# OctopusBotV3R1.net
KiCad netlist of a schematic drawn in Altium Designer
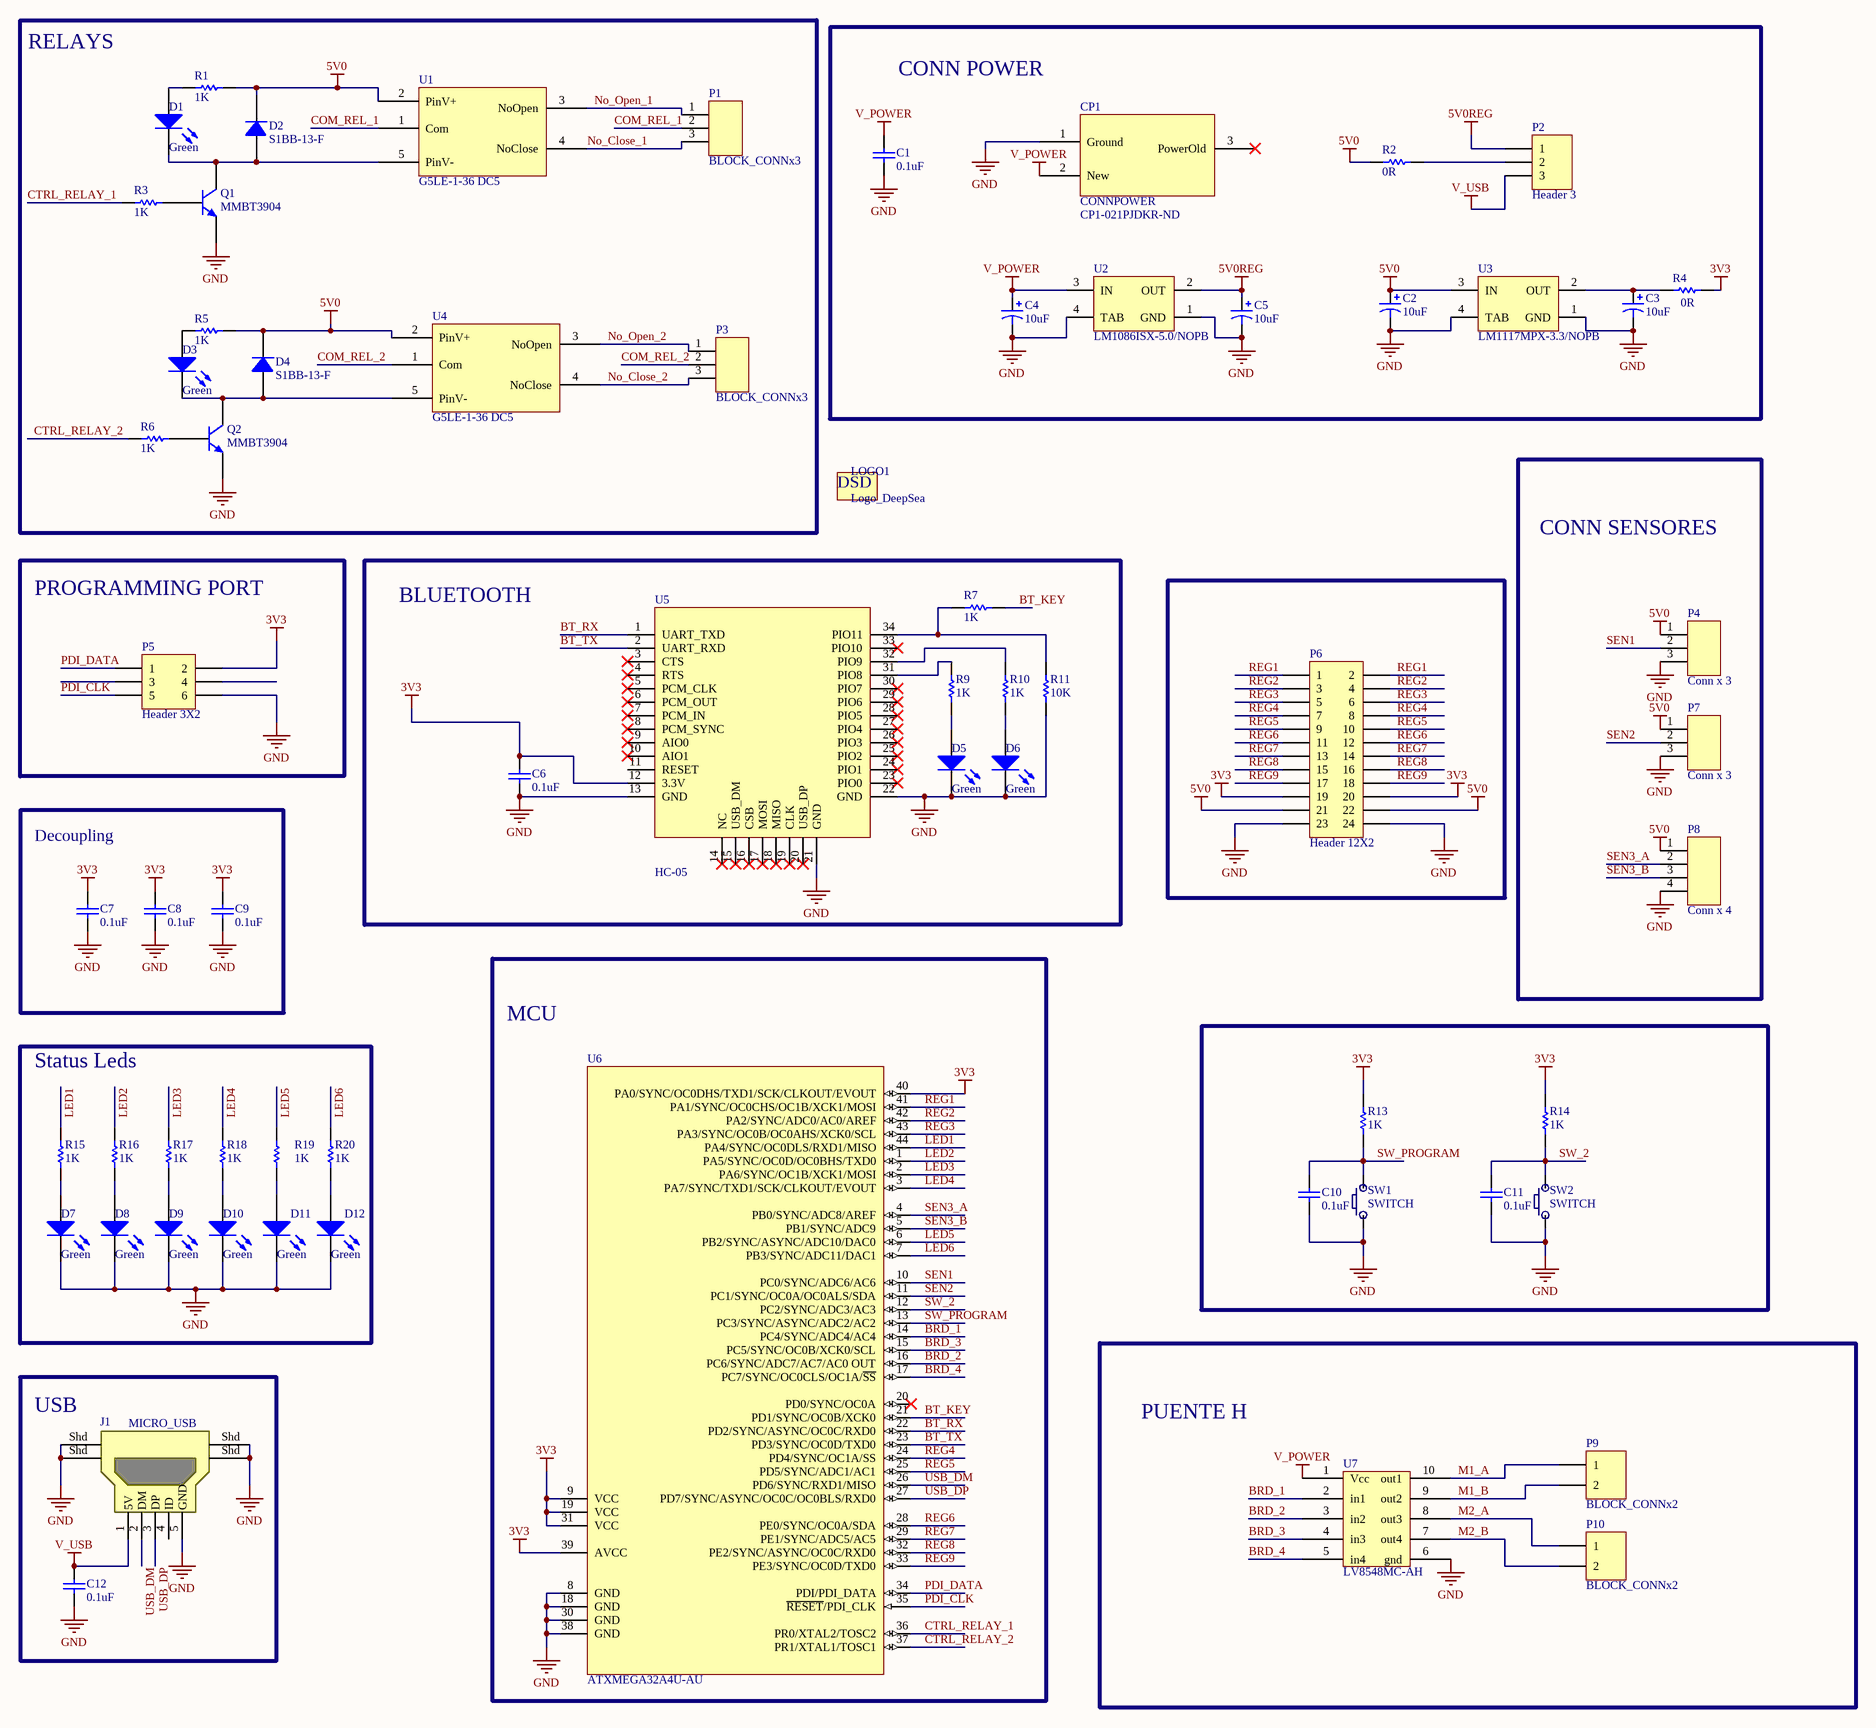
[diagram p0: OctopusBotV3R1.SchDoc]

(export (version "E")
  (design (tool "Eeschema 10.0.6"))
  (components
    (comp (ref "C1") (value "0.1uF") (footprint "C0603_N") (libsource (lib "General") (part "C_SMD")))
    (comp (ref "C2") (value "10uF") (footprint "C_TANT_A_3216_N") (libsource (lib "General") (part "CP_SMD")))
    (comp (ref "C3") (value "10uF") (footprint "C_TANT_A_3216_N") (libsource (lib "General") (part "CP_SMD")))
    (comp (ref "C4") (value "10uF") (footprint "C_TANT_A_3216_N") (libsource (lib "General") (part "CP_SMD")))
    (comp (ref "C5") (value "10uF") (footprint "C_TANT_A_3216_N") (libsource (lib "General") (part "CP_SMD")))
    (comp (ref "C6") (value "0.1uF") (footprint "C0603_N") (libsource (lib "General") (part "C_SMD")))
    (comp (ref "C7") (value "0.1uF") (footprint "C0603_N") (libsource (lib "General") (part "C_SMD")))
    (comp (ref "C8") (value "0.1uF") (footprint "C0603_N") (libsource (lib "General") (part "C_SMD")))
    (comp (ref "C9") (value "0.1uF") (footprint "C0603_N") (libsource (lib "General") (part "C_SMD")))
    (comp (ref "C10") (value "0.1uF") (footprint "C0603_N") (libsource (lib "General") (part "C_SMD")))
    (comp (ref "C11") (value "0.1uF") (footprint "C0603_N") (libsource (lib "General") (part "C_SMD")))
    (comp (ref "C12") (value "0.1uF") (footprint "C0603_N") (libsource (lib "General") (part "C_SMD")))
    (comp (ref "CP1")
      (value "CONNPOWER")
      (footprint "CONNPOWER")
      (fields (field (name "SUPPLIER PART NUMBER 1") "CP1-021PJDKR-ND"))
      (libsource (lib "General") (part "CONNPOWER"))
    )
    (comp (ref "D1")
      (value "Green")
      (footprint "R0603_N")
      (fields (field (name "COLOR") "Green"))
      (libsource (lib "discrete") (part "LED_SMD"))
    )
    (comp (ref "D2")
      (value "S1BB-13-F")
      (footprint "SMB_M")
      (description "DIODE GEN PURPOSE 100V 1A SMB")
      (fields (field (name "MANUFACTURER") "Diodes Incorporated"))
      (libsource (lib "General") (part "S1BB-13-F"))
    )
    (comp (ref "D3")
      (value "Green")
      (footprint "R0603_N")
      (fields (field (name "COLOR") "Green"))
      (libsource (lib "discrete") (part "LED_SMD"))
    )
    (comp (ref "D4")
      (value "S1BB-13-F")
      (footprint "SMB_M")
      (description "DIODE GEN PURPOSE 100V 1A SMB")
      (fields (field (name "MANUFACTURER") "Diodes Incorporated"))
      (libsource (lib "General") (part "S1BB-13-F"))
    )
    (comp (ref "D5")
      (value "Green")
      (footprint "R0603_N")
      (fields (field (name "COLOR") "Green"))
      (libsource (lib "discrete") (part "LED_SMD"))
    )
    (comp (ref "D6")
      (value "Green")
      (footprint "R0603_N")
      (fields (field (name "COLOR") "Green"))
      (libsource (lib "discrete") (part "LED_SMD"))
    )
    (comp (ref "D7")
      (value "Green")
      (footprint "R0603_N")
      (fields (field (name "COLOR") "Green"))
      (libsource (lib "discrete") (part "LED_SMD"))
    )
    (comp (ref "D8")
      (value "Green")
      (footprint "R0603_N")
      (fields (field (name "COLOR") "Green"))
      (libsource (lib "discrete") (part "LED_SMD"))
    )
    (comp (ref "D9")
      (value "Green")
      (footprint "R0603_N")
      (fields (field (name "COLOR") "Green"))
      (libsource (lib "discrete") (part "LED_SMD"))
    )
    (comp (ref "D10")
      (value "Green")
      (footprint "R0603_N")
      (fields (field (name "COLOR") "Green"))
      (libsource (lib "discrete") (part "LED_SMD"))
    )
    (comp (ref "D11")
      (value "Green")
      (footprint "R0603_N")
      (fields (field (name "COLOR") "Green"))
      (libsource (lib "discrete") (part "LED_SMD"))
    )
    (comp (ref "D12")
      (value "Green")
      (footprint "R0603_N")
      (fields (field (name "COLOR") "Green"))
      (libsource (lib "discrete") (part "LED_SMD"))
    )
    (comp (ref "J1")
      (value "MICRO_USB")
      (footprint "USB_MICRO_SMD")
      (description "CONN USB MICRO B RECPT SMT R/A")
      (fields (field (name "MANUFACTURER") "FCI") (field (name "MANUFACTURER PART NUMBER") "10118194-0001LF"))
      (libsource (lib "General") (part "MICRO_USB"))
    )
    (comp (ref "LOGO1")
      (value "Logo_DeepSea")
      (footprint "DeepSea_logo1")
      (libsource (lib "General") (part "Logo_DeepSea"))
    )
    (comp (ref "P1")
      (value "BLOCK_CONNx3")
      (footprint "BLOCK_CONNx3")
      (description "TERM BLOCK 5.08MM VERT 3POS PCB")
      (fields
        (field (name "MANUFACTURER") "On Shore Technology Inc")
        (field (name "MANUFACTURER PART NUMBER") "OSTTC032162")
      )
      (libsource (lib "General") (part "BLOCK_CONNx3"))
    )
    (comp (ref "P2")
      (value "Header 3")
      (footprint "HDR1X3")
      (description "Header, 3-Pin")
      (fields (field (name "PUBLISHER") "Altium Limited"))
      (libsource (lib "Miscellaneous Connectors") (part "Header 3"))
    )
    (comp (ref "P3")
      (value "BLOCK_CONNx3")
      (footprint "BLOCK_CONNx3")
      (description "TERM BLOCK 5.08MM VERT 3POS PCB")
      (fields
        (field (name "MANUFACTURER") "On Shore Technology Inc")
        (field (name "MANUFACTURER PART NUMBER") "OSTTC032162")
      )
      (libsource (lib "General") (part "BLOCK_CONNx3"))
    )
    (comp (ref "P4")
      (value "Conn x 3")
      (footprint "conn x 3")
      (description "CONN HEADER VERT 3POS .100 TIN")
      (fields
        (field (name "MANUFACTURER") "TE Connectivity")
        (field (name "MANUFACTURER PART NUMBER") "640456-3")
      )
      (libsource (lib "General") (part "Conn x 3"))
    )
    (comp (ref "P5")
      (value "Header 3X2")
      (footprint "HDR2X3")
      (description "Header, 3-Pin, Dual row")
      (fields (field (name "PUBLISHER") "Altium Limited"))
      (libsource (lib "Miscellaneous Connectors") (part "Header 3X2"))
    )
    (comp (ref "P6")
      (value "Header 12X2")
      (footprint "HDR2X12")
      (description "Header, 12-Pin, Dual row")
      (fields (field (name "PUBLISHER") "Altium Limited"))
      (libsource (lib "Miscellaneous Connectors") (part "Header 12X2"))
    )
    (comp (ref "P7")
      (value "Conn x 3")
      (footprint "conn x 3")
      (description "CONN HEADER VERT 3POS .100 TIN")
      (fields
        (field (name "MANUFACTURER") "TE Connectivity")
        (field (name "MANUFACTURER PART NUMBER") "640456-3")
      )
      (libsource (lib "General") (part "Conn x 3"))
    )
    (comp (ref "P8")
      (value "Conn x 4")
      (footprint "conn x 4")
      (description "CONN HEADER VERT 4POS .100 TIN")
      (fields
        (field (name "MANUFACTURER") "TE Connectivity")
        (field (name "MANUFACTURER PART NUMBER") "640454-4")
      )
      (libsource (lib "General") (part "Conn x 4"))
    )
    (comp (ref "P9")
      (value "BLOCK_CONNx2")
      (footprint "BLOCK_CONNX2")
      (description "TERM BLOCK 5.08MM VERT 2POS PCB")
      (fields
        (field (name "MANUFACTURER") "On Shore Technology Inc")
        (field (name "MANUFACTURER PART NUMBER") "OSTTC022162")
      )
      (libsource (lib "General") (part "BLOCK_CONNx2"))
    )
    (comp (ref "P10")
      (value "BLOCK_CONNx2")
      (footprint "BLOCK_CONNX2")
      (description "TERM BLOCK 5.08MM VERT 2POS PCB")
      (fields
        (field (name "MANUFACTURER") "On Shore Technology Inc")
        (field (name "MANUFACTURER PART NUMBER") "OSTTC022162")
      )
      (libsource (lib "General") (part "BLOCK_CONNx2"))
    )
    (comp (ref "Q1")
      (value "MMBT3904")
      (footprint "SOT23_N")
      (description "NPN Switching Transistor")
      (fields
        (field (name "MANUFACTURER") "Micro Commercial Co")
        (field (name "MANUFACTURER PART NUMBER") "MMBT3904-TP")
        (field (name "PUBLISHER") "Altium Limited")
      )
      (libsource (lib "General") (part "MMBT3904"))
    )
    (comp (ref "Q2")
      (value "MMBT3904")
      (footprint "SOT23_N")
      (description "NPN Switching Transistor")
      (fields
        (field (name "MANUFACTURER") "Micro Commercial Co")
        (field (name "MANUFACTURER PART NUMBER") "MMBT3904-TP")
        (field (name "PUBLISHER") "Altium Limited")
      )
      (libsource (lib "General") (part "MMBT3904"))
    )
    (comp (ref "R1") (value "1K") (footprint "R0603_N") (libsource (lib "discrete") (part "R_SMD")))
    (comp (ref "R2") (value "0R") (footprint "R0603_N") (libsource (lib "discrete") (part "R_SMD")))
    (comp (ref "R3") (value "1K") (footprint "R0603_N") (libsource (lib "discrete") (part "R_SMD")))
    (comp (ref "R4") (value "0R") (footprint "R0603_N") (libsource (lib "discrete") (part "R_SMD")))
    (comp (ref "R5") (value "1K") (footprint "R0603_N") (libsource (lib "discrete") (part "R_SMD")))
    (comp (ref "R6") (value "1K") (footprint "R0603_N") (libsource (lib "discrete") (part "R_SMD")))
    (comp (ref "R7") (value "1K") (footprint "R0603_N") (libsource (lib "discrete") (part "R_SMD")))
    (comp (ref "R9") (value "1K") (footprint "R0603_N") (libsource (lib "discrete") (part "R_SMD")))
    (comp (ref "R10") (value "1K") (footprint "R0603_N") (libsource (lib "discrete") (part "R_SMD")))
    (comp (ref "R11") (value "10K") (footprint "R0603_N") (libsource (lib "discrete") (part "R_SMD")))
    (comp (ref "R13") (value "1K") (footprint "R0603_N") (libsource (lib "discrete") (part "R_SMD")))
    (comp (ref "R14") (value "1K") (footprint "R0603_N") (libsource (lib "discrete") (part "R_SMD")))
    (comp (ref "R15") (value "1K") (footprint "R0603_N") (libsource (lib "discrete") (part "R_SMD")))
    (comp (ref "R16") (value "1K") (footprint "R0603_N") (libsource (lib "discrete") (part "R_SMD")))
    (comp (ref "R17") (value "1K") (footprint "R0603_N") (libsource (lib "discrete") (part "R_SMD")))
    (comp (ref "R18") (value "1K") (footprint "R0603_N") (libsource (lib "discrete") (part "R_SMD")))
    (comp (ref "R19") (value "1K") (footprint "R0603_N") (libsource (lib "discrete") (part "R_SMD")))
    (comp (ref "R20") (value "1K") (footprint "R0603_N") (libsource (lib "discrete") (part "R_SMD")))
    (comp (ref "SW1")
      (value "SWITCH")
      (footprint "swich_foot")
      (description "SWITCH TACTILE SPST-NO 0.05A 12V")
      (fields
        (field (name "MANUFACTURER") "TE Connectivity")
        (field (name "MANUFACTURER PART NUMBER") "FSM4JSMATR")
      )
      (libsource (lib "General") (part "SWITCH"))
    )
    (comp (ref "SW2")
      (value "SWITCH")
      (footprint "swich_foot")
      (description "SWITCH TACTILE SPST-NO 0.05A 12V")
      (fields
        (field (name "MANUFACTURER") "TE Connectivity")
        (field (name "MANUFACTURER PART NUMBER") "FSM4JSMATR")
      )
      (libsource (lib "General") (part "SWITCH"))
    )
    (comp (ref "U1")
      (value "G5LE-1-36 DC5")
      (footprint "Relay 5V")
      (description "RELAY GEN PURPOSE SPDT 10A 5V")
      (fields (field (name "MANUFACTURER") "Omron Electronics Inc-EMC Div"))
      (libsource (lib "General") (part "G5LE-1-36 DC5"))
    )
    (comp (ref "U2")
      (value "LM1086ISX-5.0/NOPB")
      (footprint "TS3B_N")
      (description "1.5A Low Dropout Positive Regulators, 3-pin TO-263, Pb-Free")
      (fields
        (field (name "MANUFACTURER") "National Semiconductor")
        (field (name "PUBLISHER") "Altium Limited")
      )
      (libsource (lib "General") (part "LM1086ISX-5.0/NOPB"))
    )
    (comp (ref "U3")
      (value "LM1117MPX-3.3/NOPB")
      (footprint "MP04A_N")
      (description "800mA Low-Dropout Linear Regulator, 4-pin SOT-223, Pb-Free")
      (fields
        (field (name "MANUFACTURER") "National Semiconductor")
        (field (name "PUBLISHER") "Altium Limited")
      )
      (libsource (lib "General") (part "LM1117MPX-3.3/NOPB"))
    )
    (comp (ref "U4")
      (value "G5LE-1-36 DC5")
      (footprint "Relay 5V")
      (description "RELAY GEN PURPOSE SPDT 10A 5V")
      (fields (field (name "MANUFACTURER") "Omron Electronics Inc-EMC Div"))
      (libsource (lib "General") (part "G5LE-1-36 DC5"))
    )
    (comp (ref "U5")
      (value "HC-05")
      (footprint "HC-05")
      (description "Bluetooth RS232 module")
      (libsource (lib "General") (part "HC-05"))
    )
    (comp (ref "U6")
      (value "ATXMEGA32A4U-AU")
      (footprint "44A_N")
      (description "IC MCU 8BIT 32KB FLASH 44TQFP")
      (fields (field (name "MANUFACTURER") "Atmel"))
      (libsource (lib "General") (part "ATXMEGA32A4U-AU"))
    )
    (comp (ref "U7")
      (value "LV8548MC-AH")
      (footprint "SOIC10")
      (description "IC MOTOR DRIVER PAR MFP10S")
      (fields (field (name "MANUFACTURER") "ON Semiconductor"))
      (libsource (lib "General") (part "LV8548MC-AH"))
    )
  )
  (nets
    (net (code "1") (name "/BRD_1") (class "Default")
      (node (ref "U6") (pin "14") (pinfunction "PC4/SYNC/ADC4/AC4_14") (pintype "bidirectional"))
      (node (ref "U7") (pin "2") (pinfunction "in1_2") (pintype "passive"))
    )
    (net (code "2") (name "/BRD_2") (class "Default")
      (node (ref "U6") (pin "16") (pinfunction "PC6/SYNC/ADC7/AC7/AC0_OUT_16") (pintype "bidirectional"))
      (node (ref "U7") (pin "3") (pinfunction "in2_3") (pintype "passive"))
    )
    (net (code "3") (name "/BRD_3") (class "Default")
      (node (ref "U6") (pin "15") (pinfunction "PC5/SYNC/OC0B/XCK0/SCL_15") (pintype "bidirectional"))
      (node (ref "U7") (pin "4") (pinfunction "in3_4") (pintype "passive"))
    )
    (net (code "4") (name "/BRD_4") (class "Default")
      (node (ref "U6") (pin "17") (pinfunction "PC7/SYNC/OC0CLS/OC1A/~{SS}_17") (pintype "bidirectional"))
      (node (ref "U7") (pin "5") (pinfunction "in4_5") (pintype "passive"))
    )
    (net (code "5") (name "/BT_KEY") (class "Default")
      (node (ref "R7") (pin "1") (pinfunction "1_1") (pintype "passive"))
      (node (ref "U6") (pin "21") (pinfunction "PD1/SYNC/OC0B/XCK0_21") (pintype "bidirectional"))
    )
    (net (code "6") (name "/BT_RX") (class "Default")
      (node (ref "U5") (pin "1") (pinfunction "UART_TXD_1") (pintype "passive"))
      (node (ref "U6") (pin "22") (pinfunction "PD2/SYNC/ASYNC/OC0C/RXD0_22") (pintype "bidirectional"))
    )
    (net (code "7") (name "/BT_TX") (class "Default")
      (node (ref "U5") (pin "2") (pinfunction "UART_RXD_2") (pintype "passive"))
      (node (ref "U6") (pin "23") (pinfunction "PD3/SYNC/OC0D/TXD0_23") (pintype "bidirectional"))
    )
    (net (code "8") (name "/COM_REL_1") (class "Default")
      (node (ref "P1") (pin "2") (pintype "passive"))
      (node (ref "U1") (pin "1") (pinfunction "Com_1") (pintype "passive"))
    )
    (net (code "9") (name "/COM_REL_2") (class "Default")
      (node (ref "P3") (pin "2") (pintype "passive"))
      (node (ref "U4") (pin "1") (pinfunction "Com_1") (pintype "passive"))
    )
    (net (code "10") (name "/CTRL_RELAY_1") (class "Default")
      (node (ref "R3") (pin "1") (pinfunction "1_1") (pintype "passive"))
      (node (ref "U6") (pin "36") (pinfunction "PR0/XTAL2/TOSC2_36") (pintype "bidirectional"))
    )
    (net (code "11") (name "/CTRL_RELAY_2") (class "Default")
      (node (ref "R6") (pin "1") (pinfunction "1_1") (pintype "passive"))
      (node (ref "U6") (pin "37") (pinfunction "PR1/XTAL1/TOSC1_37") (pintype "bidirectional"))
    )
    (net (code "12") (name "/LED1") (class "Default")
      (node (ref "R15") (pin "1") (pinfunction "1_1") (pintype "passive"))
      (node (ref "U6") (pin "44") (pinfunction "PA4/SYNC/OC0DLS/RXD1/MISO_44") (pintype "bidirectional"))
    )
    (net (code "13") (name "/LED2") (class "Default")
      (node (ref "R16") (pin "1") (pinfunction "1_1") (pintype "passive"))
      (node (ref "U6") (pin "1") (pinfunction "PA5/SYNC/OC0D/OC0BHS/TXD0_1") (pintype "bidirectional"))
    )
    (net (code "14") (name "/LED3") (class "Default")
      (node (ref "R17") (pin "1") (pinfunction "1_1") (pintype "passive"))
      (node (ref "U6") (pin "2") (pinfunction "PA6/SYNC/OC1B/XCK1/MOSI_2") (pintype "bidirectional"))
    )
    (net (code "15") (name "/LED4") (class "Default")
      (node (ref "R18") (pin "1") (pinfunction "1_1") (pintype "passive"))
      (node (ref "U6") (pin "3") (pinfunction "PA7/SYNC/TXD1/SCK/CLKOUT/EVOUT_3") (pintype "bidirectional"))
    )
    (net (code "16") (name "/LED5") (class "Default")
      (node (ref "R19") (pin "1") (pinfunction "1_1") (pintype "passive"))
      (node (ref "U6") (pin "6") (pinfunction "PB2/SYNC/ASYNC/ADC10/DAC0_6") (pintype "bidirectional"))
    )
    (net (code "17") (name "/LED6") (class "Default")
      (node (ref "R20") (pin "1") (pinfunction "1_1") (pintype "passive"))
      (node (ref "U6") (pin "7") (pinfunction "PB3/SYNC/ADC11/DAC1_7") (pintype "bidirectional"))
    )
    (net (code "18") (name "/M1_A") (class "Default")
      (node (ref "P9") (pin "1") (pinfunction "1_1") (pintype "passive"))
      (node (ref "U7") (pin "10") (pinfunction "out1_10") (pintype "passive"))
    )
    (net (code "19") (name "/M1_B") (class "Default")
      (node (ref "P9") (pin "2") (pinfunction "2_2") (pintype "passive"))
      (node (ref "U7") (pin "9") (pinfunction "out2_9") (pintype "passive"))
    )
    (net (code "20") (name "/M2_A") (class "Default")
      (node (ref "P10") (pin "1") (pinfunction "1_1") (pintype "passive"))
      (node (ref "U7") (pin "8") (pinfunction "out3_8") (pintype "passive"))
    )
    (net (code "21") (name "/M2_B") (class "Default")
      (node (ref "P10") (pin "2") (pinfunction "2_2") (pintype "passive"))
      (node (ref "U7") (pin "7") (pinfunction "out4_7") (pintype "passive"))
    )
    (net (code "22") (name "/No_Close_1") (class "Default")
      (node (ref "P1") (pin "3") (pintype "passive"))
      (node (ref "U1") (pin "4") (pinfunction "NoClose_4") (pintype "passive"))
    )
    (net (code "23") (name "/No_Close_2") (class "Default")
      (node (ref "P3") (pin "3") (pintype "passive"))
      (node (ref "U4") (pin "4") (pinfunction "NoClose_4") (pintype "passive"))
    )
    (net (code "24") (name "/No_Open_1") (class "Default")
      (node (ref "P1") (pin "1") (pintype "passive"))
      (node (ref "U1") (pin "3") (pinfunction "NoOpen_3") (pintype "passive"))
    )
    (net (code "25") (name "/No_Open_2") (class "Default")
      (node (ref "P3") (pin "1") (pintype "passive"))
      (node (ref "U4") (pin "3") (pinfunction "NoOpen_3") (pintype "passive"))
    )
    (net (code "26") (name "/PDI_CLK") (class "Default")
      (node (ref "P5") (pin "5") (pinfunction "5_5") (pintype "passive"))
      (node (ref "U6") (pin "35") (pinfunction "~{RESET}/PDI_CLK_35") (pintype "input"))
    )
    (net (code "27") (name "/PDI_DATA") (class "Default")
      (node (ref "P5") (pin "1") (pinfunction "1_1") (pintype "passive"))
      (node (ref "U6") (pin "34") (pinfunction "PDI/PDI_DATA_34") (pintype "bidirectional"))
    )
    (net (code "28") (name "/REG1") (class "Default")
      (node (ref "P6") (pin "1") (pinfunction "1_1") (pintype "passive"))
      (node (ref "P6") (pin "2") (pinfunction "2_2") (pintype "passive"))
      (node (ref "U6") (pin "41") (pinfunction "PA1/SYNC/OC0CHS/OC1B/XCK1/MOSI_41") (pintype "bidirectional"))
    )
    (net (code "29") (name "/REG2") (class "Default")
      (node (ref "P6") (pin "3") (pinfunction "3_3") (pintype "passive"))
      (node (ref "P6") (pin "4") (pinfunction "4_4") (pintype "passive"))
      (node (ref "U6") (pin "42") (pinfunction "PA2/SYNC/ADC0/AC0/AREF_42") (pintype "bidirectional"))
    )
    (net (code "30") (name "/REG3") (class "Default")
      (node (ref "P6") (pin "5") (pinfunction "5_5") (pintype "passive"))
      (node (ref "P6") (pin "6") (pinfunction "6_6") (pintype "passive"))
      (node (ref "U6") (pin "43") (pinfunction "PA3/SYNC/OC0B/OC0AHS/XCK0/SCL_43") (pintype "bidirectional"))
    )
    (net (code "31") (name "/REG4") (class "Default")
      (node (ref "P6") (pin "7") (pinfunction "7_7") (pintype "passive"))
      (node (ref "P6") (pin "8") (pinfunction "8_8") (pintype "passive"))
      (node (ref "U6") (pin "24") (pinfunction "PD4/SYNC/OC1A/SS_24") (pintype "bidirectional"))
    )
    (net (code "32") (name "/REG5") (class "Default")
      (node (ref "P6") (pin "10") (pinfunction "10_10") (pintype "passive"))
      (node (ref "P6") (pin "9") (pinfunction "9_9") (pintype "passive"))
      (node (ref "U6") (pin "25") (pinfunction "PD5/SYNC/ADC1/AC1_25") (pintype "bidirectional"))
    )
    (net (code "33") (name "/REG6") (class "Default")
      (node (ref "P6") (pin "11") (pinfunction "11_11") (pintype "passive"))
      (node (ref "P6") (pin "12") (pinfunction "12_12") (pintype "passive"))
      (node (ref "U6") (pin "28") (pinfunction "PE0/SYNC/OC0A/SDA_28") (pintype "bidirectional"))
    )
    (net (code "34") (name "/REG7") (class "Default")
      (node (ref "P6") (pin "13") (pinfunction "13_13") (pintype "passive"))
      (node (ref "P6") (pin "14") (pinfunction "14_14") (pintype "passive"))
      (node (ref "U6") (pin "29") (pinfunction "PE1/SYNC/ADC5/AC5_29") (pintype "bidirectional"))
    )
    (net (code "35") (name "/REG8") (class "Default")
      (node (ref "P6") (pin "15") (pinfunction "15_15") (pintype "passive"))
      (node (ref "P6") (pin "16") (pinfunction "16_16") (pintype "passive"))
      (node (ref "U6") (pin "32") (pinfunction "PE2/SYNC/ASYNC/OC0C/RXD0_32") (pintype "bidirectional"))
    )
    (net (code "36") (name "/REG9") (class "Default")
      (node (ref "P6") (pin "17") (pinfunction "17_17") (pintype "passive"))
      (node (ref "P6") (pin "18") (pinfunction "18_18") (pintype "passive"))
      (node (ref "U6") (pin "33") (pinfunction "PE3/SYNC/OC0D/TXD0_33") (pintype "bidirectional"))
    )
    (net (code "37") (name "/SEN1") (class "Default")
      (node (ref "P4") (pin "2") (pintype "passive"))
      (node (ref "U6") (pin "10") (pinfunction "PC0/SYNC/ADC6/AC6_10") (pintype "bidirectional"))
    )
    (net (code "38") (name "/SEN2") (class "Default")
      (node (ref "P7") (pin "2") (pintype "passive"))
      (node (ref "U6") (pin "11") (pinfunction "PC1/SYNC/OC0A/OC0ALS/SDA_11") (pintype "bidirectional"))
    )
    (net (code "39") (name "/SEN3_A") (class "Default")
      (node (ref "P8") (pin "2") (pintype "passive"))
      (node (ref "U6") (pin "4") (pinfunction "PB0/SYNC/ADC8/AREF_4") (pintype "bidirectional"))
    )
    (net (code "40") (name "/SEN3_B") (class "Default")
      (node (ref "P8") (pin "3") (pintype "passive"))
      (node (ref "U6") (pin "5") (pinfunction "PB1/SYNC/ADC9_5") (pintype "bidirectional"))
    )
    (net (code "41") (name "/SW_2") (class "Default")
      (node (ref "C11") (pin "1") (pinfunction "1_1") (pintype "passive"))
      (node (ref "R14") (pin "1") (pinfunction "1_1") (pintype "passive"))
      (node (ref "SW2") (pin "2") (pinfunction "*_2") (pintype "passive"))
      (node (ref "U6") (pin "12") (pinfunction "PC2/SYNC/ADC3/AC3_12") (pintype "bidirectional"))
    )
    (net (code "42") (name "/SW_PROGRAM") (class "Default")
      (node (ref "C10") (pin "1") (pinfunction "1_1") (pintype "passive"))
      (node (ref "R13") (pin "1") (pinfunction "1_1") (pintype "passive"))
      (node (ref "SW1") (pin "2") (pinfunction "*_2") (pintype "passive"))
      (node (ref "U6") (pin "13") (pinfunction "PC3/SYNC/ASYNC/ADC2/AC2_13") (pintype "bidirectional"))
    )
    (net (code "43") (name "/USB_DM") (class "Default")
      (node (ref "J1") (pin "2") (pinfunction "DM_2") (pintype "passive"))
      (node (ref "U6") (pin "26") (pinfunction "PD6/SYNC/RXD1/MISO_26") (pintype "bidirectional"))
    )
    (net (code "44") (name "/USB_DP") (class "Default")
      (node (ref "J1") (pin "3") (pinfunction "DP_3") (pintype "passive"))
      (node (ref "U6") (pin "27") (pinfunction "PD7/SYNC/ASYNC/OC0C/OC0BLS/RXD0_27") (pintype "bidirectional"))
    )
    (net (code "45") (name "3V3") (class "Default")
      (node (ref "C6") (pin "2") (pinfunction "2_2") (pintype "passive"))
      (node (ref "C7") (pin "2") (pinfunction "2_2") (pintype "passive"))
      (node (ref "C8") (pin "2") (pinfunction "2_2") (pintype "passive"))
      (node (ref "C9") (pin "2") (pinfunction "2_2") (pintype "passive"))
      (node (ref "P5") (pin "2") (pinfunction "2_2") (pintype "passive"))
      (node (ref "P6") (pin "19") (pinfunction "19_19") (pintype "passive"))
      (node (ref "P6") (pin "20") (pinfunction "20_20") (pintype "passive"))
      (node (ref "R13") (pin "2") (pinfunction "2_2") (pintype "passive"))
      (node (ref "R14") (pin "2") (pinfunction "2_2") (pintype "passive"))
      (node (ref "R4") (pin "1") (pinfunction "1_1") (pintype "passive"))
      (node (ref "U5") (pin "12") (pinfunction "3.3V_12") (pintype "passive"))
      (node (ref "U6") (pin "19") (pinfunction "VCC_19") (pintype "power_in"))
      (node (ref "U6") (pin "31") (pinfunction "VCC_31") (pintype "power_in"))
      (node (ref "U6") (pin "39") (pinfunction "AVCC_39") (pintype "power_in"))
      (node (ref "U6") (pin "40") (pinfunction "PA0/SYNC/OC0DHS/TXD1/SCK/CLKOUT/EVOUT_40") (pintype "bidirectional"))
      (node (ref "U6") (pin "9") (pinfunction "VCC_9") (pintype "power_in"))
    )
    (net (code "46") (name "5V0") (class "Default")
      (node (ref "C2") (pin "1") (pinfunction "1_1") (pintype "passive"))
      (node (ref "D2") (pin "2") (pinfunction "K_2") (pintype "passive"))
      (node (ref "D4") (pin "2") (pinfunction "K_2") (pintype "passive"))
      (node (ref "P4") (pin "1") (pintype "passive"))
      (node (ref "P6") (pin "21") (pinfunction "21_21") (pintype "passive"))
      (node (ref "P6") (pin "22") (pinfunction "22_22") (pintype "passive"))
      (node (ref "P7") (pin "1") (pintype "passive"))
      (node (ref "P8") (pin "1") (pintype "passive"))
      (node (ref "R1") (pin "2") (pinfunction "2_2") (pintype "passive"))
      (node (ref "R2") (pin "2") (pinfunction "2_2") (pintype "passive"))
      (node (ref "R5") (pin "2") (pinfunction "2_2") (pintype "passive"))
      (node (ref "U1") (pin "2") (pinfunction "PinV+_2") (pintype "passive"))
      (node (ref "U3") (pin "3") (pinfunction "IN_3") (pintype "power_in"))
      (node (ref "U4") (pin "2") (pinfunction "PinV+_2") (pintype "passive"))
    )
    (net (code "47") (name "5V0REG") (class "Default")
      (node (ref "C5") (pin "1") (pinfunction "1_1") (pintype "passive"))
      (node (ref "P2") (pin "1") (pinfunction "1_1") (pintype "passive"))
      (node (ref "U2") (pin "2") (pinfunction "OUT_2") (pintype "power_in"))
    )
    (net (code "48") (name "GND") (class "Default")
      (node (ref "C1") (pin "1") (pinfunction "1_1") (pintype "passive"))
      (node (ref "C10") (pin "2") (pinfunction "2_2") (pintype "passive"))
      (node (ref "C11") (pin "2") (pinfunction "2_2") (pintype "passive"))
      (node (ref "C12") (pin "1") (pinfunction "1_1") (pintype "passive"))
      (node (ref "C2") (pin "2") (pinfunction "2_2") (pintype "passive"))
      (node (ref "C3") (pin "2") (pinfunction "2_2") (pintype "passive"))
      (node (ref "C4") (pin "2") (pinfunction "2_2") (pintype "passive"))
      (node (ref "C5") (pin "2") (pinfunction "2_2") (pintype "passive"))
      (node (ref "C6") (pin "1") (pinfunction "1_1") (pintype "passive"))
      (node (ref "C7") (pin "1") (pinfunction "1_1") (pintype "passive"))
      (node (ref "C8") (pin "1") (pinfunction "1_1") (pintype "passive"))
      (node (ref "C9") (pin "1") (pinfunction "1_1") (pintype "passive"))
      (node (ref "CP1") (pin "1") (pinfunction "Ground_1") (pintype "passive"))
      (node (ref "D10") (pin "2") (pinfunction "K_2") (pintype "passive"))
      (node (ref "D11") (pin "2") (pinfunction "K_2") (pintype "passive"))
      (node (ref "D12") (pin "2") (pinfunction "K_2") (pintype "passive"))
      (node (ref "D5") (pin "2") (pinfunction "K_2") (pintype "passive"))
      (node (ref "D6") (pin "2") (pinfunction "K_2") (pintype "passive"))
      (node (ref "D7") (pin "2") (pinfunction "K_2") (pintype "passive"))
      (node (ref "D8") (pin "2") (pinfunction "K_2") (pintype "passive"))
      (node (ref "D9") (pin "2") (pinfunction "K_2") (pintype "passive"))
      (node (ref "J1") (pin "5") (pinfunction "GND_5") (pintype "power_in"))
      (node (ref "J1") (pin "Shd") (pinfunction "6_Shd") (pintype "passive"))
      (node (ref "P4") (pin "3") (pintype "passive"))
      (node (ref "P5") (pin "6") (pinfunction "6_6") (pintype "passive"))
      (node (ref "P6") (pin "23") (pinfunction "23_23") (pintype "passive"))
      (node (ref "P6") (pin "24") (pinfunction "24_24") (pintype "passive"))
      (node (ref "P7") (pin "3") (pintype "passive"))
      (node (ref "P8") (pin "4") (pintype "passive"))
      (node (ref "Q1") (pin "2") (pinfunction "E_2") (pintype "passive"))
      (node (ref "Q2") (pin "2") (pinfunction "E_2") (pintype "passive"))
      (node (ref "R11") (pin "2") (pinfunction "2_2") (pintype "passive"))
      (node (ref "SW1") (pin "1") (pinfunction "*_1") (pintype "passive"))
      (node (ref "SW2") (pin "1") (pinfunction "*_1") (pintype "passive"))
      (node (ref "U2") (pin "1") (pinfunction "GND_1") (pintype "power_in"))
      (node (ref "U2") (pin "4") (pinfunction "TAB_4") (pintype "power_in"))
      (node (ref "U3") (pin "1") (pinfunction "GND_1") (pintype "power_in"))
      (node (ref "U3") (pin "4") (pinfunction "TAB_4") (pintype "power_in"))
      (node (ref "U5") (pin "13") (pinfunction "GND_13") (pintype "passive"))
      (node (ref "U5") (pin "21") (pinfunction "GND_21") (pintype "passive"))
      (node (ref "U5") (pin "22") (pinfunction "GND_22") (pintype "passive"))
      (node (ref "U6") (pin "18") (pinfunction "GND_18") (pintype "power_in"))
      (node (ref "U6") (pin "30") (pinfunction "GND_30") (pintype "power_in"))
      (node (ref "U6") (pin "38") (pinfunction "GND_38") (pintype "power_in"))
      (node (ref "U6") (pin "8") (pinfunction "GND_8") (pintype "power_in"))
      (node (ref "U7") (pin "6") (pinfunction "gnd_6") (pintype "passive"))
    )
    (net (code "49") (name "Net-(D1-A)") (class "Default")
      (node (ref "D1") (pin "1") (pinfunction "A_1") (pintype "passive"))
      (node (ref "R1") (pin "1") (pinfunction "1_1") (pintype "passive"))
    )
    (net (code "50") (name "Net-(D1-K)") (class "Default")
      (node (ref "D1") (pin "2") (pinfunction "K_2") (pintype "passive"))
      (node (ref "D2") (pin "1") (pinfunction "A_1") (pintype "passive"))
      (node (ref "Q1") (pin "3") (pinfunction "C_3") (pintype "passive"))
      (node (ref "U1") (pin "5") (pinfunction "PinV-_5") (pintype "passive"))
    )
    (net (code "51") (name "Net-(D3-A)") (class "Default")
      (node (ref "D3") (pin "1") (pinfunction "A_1") (pintype "passive"))
      (node (ref "R5") (pin "1") (pinfunction "1_1") (pintype "passive"))
    )
    (net (code "52") (name "Net-(D3-K)") (class "Default")
      (node (ref "D3") (pin "2") (pinfunction "K_2") (pintype "passive"))
      (node (ref "D4") (pin "1") (pinfunction "A_1") (pintype "passive"))
      (node (ref "Q2") (pin "3") (pinfunction "C_3") (pintype "passive"))
      (node (ref "U4") (pin "5") (pinfunction "PinV-_5") (pintype "passive"))
    )
    (net (code "53") (name "Net-(D5-A)") (class "Default")
      (node (ref "D5") (pin "1") (pinfunction "A_1") (pintype "passive"))
      (node (ref "R9") (pin "2") (pinfunction "2_2") (pintype "passive"))
    )
    (net (code "54") (name "Net-(D6-A)") (class "Default")
      (node (ref "D6") (pin "1") (pinfunction "A_1") (pintype "passive"))
      (node (ref "R10") (pin "2") (pinfunction "2_2") (pintype "passive"))
    )
    (net (code "55") (name "Net-(D7-A)") (class "Default")
      (node (ref "D7") (pin "1") (pinfunction "A_1") (pintype "passive"))
      (node (ref "R15") (pin "2") (pinfunction "2_2") (pintype "passive"))
    )
    (net (code "56") (name "Net-(D8-A)") (class "Default")
      (node (ref "D8") (pin "1") (pinfunction "A_1") (pintype "passive"))
      (node (ref "R16") (pin "2") (pinfunction "2_2") (pintype "passive"))
    )
    (net (code "57") (name "Net-(D9-A)") (class "Default")
      (node (ref "D9") (pin "1") (pinfunction "A_1") (pintype "passive"))
      (node (ref "R17") (pin "2") (pinfunction "2_2") (pintype "passive"))
    )
    (net (code "58") (name "Net-(D10-A)") (class "Default")
      (node (ref "D10") (pin "1") (pinfunction "A_1") (pintype "passive"))
      (node (ref "R18") (pin "2") (pinfunction "2_2") (pintype "passive"))
    )
    (net (code "59") (name "Net-(D11-A)") (class "Default")
      (node (ref "D11") (pin "1") (pinfunction "A_1") (pintype "passive"))
      (node (ref "R19") (pin "2") (pinfunction "2_2") (pintype "passive"))
    )
    (net (code "60") (name "Net-(D12-A)") (class "Default")
      (node (ref "D12") (pin "1") (pinfunction "A_1") (pintype "passive"))
      (node (ref "R20") (pin "2") (pinfunction "2_2") (pintype "passive"))
    )
    (net (code "61") (name "Net-(P2-Pad2)") (class "Default")
      (node (ref "P2") (pin "2") (pinfunction "2_2") (pintype "passive"))
      (node (ref "R2") (pin "1") (pinfunction "1_1") (pintype "passive"))
    )
    (net (code "62") (name "Net-(Q1-B)") (class "Default")
      (node (ref "Q1") (pin "1") (pinfunction "B_1") (pintype "passive"))
      (node (ref "R3") (pin "2") (pinfunction "2_2") (pintype "passive"))
    )
    (net (code "63") (name "Net-(Q2-B)") (class "Default")
      (node (ref "Q2") (pin "1") (pinfunction "B_1") (pintype "passive"))
      (node (ref "R6") (pin "2") (pinfunction "2_2") (pintype "passive"))
    )
    (net (code "64") (name "Net-(U3-OUT)") (class "Default")
      (node (ref "C3") (pin "1") (pinfunction "1_1") (pintype "passive"))
      (node (ref "R4") (pin "2") (pinfunction "2_2") (pintype "passive"))
      (node (ref "U3") (pin "2") (pinfunction "OUT_2") (pintype "power_in"))
    )
    (net (code "65") (name "Net-(U5-PIO8)") (class "Default")
      (node (ref "R9") (pin "1") (pinfunction "1_1") (pintype "passive"))
      (node (ref "U5") (pin "31") (pinfunction "PIO8_31") (pintype "passive"))
    )
    (net (code "66") (name "Net-(U5-PIO9)") (class "Default")
      (node (ref "R10") (pin "1") (pinfunction "1_1") (pintype "passive"))
      (node (ref "U5") (pin "32") (pinfunction "PIO9_32") (pintype "passive"))
    )
    (net (code "67") (name "Net-(U5-PIO11)") (class "Default")
      (node (ref "R11") (pin "1") (pinfunction "1_1") (pintype "passive"))
      (node (ref "R7") (pin "2") (pinfunction "2_2") (pintype "passive"))
      (node (ref "U5") (pin "34") (pinfunction "PIO11_34") (pintype "passive"))
    )
    (net (code "68") (name "V_POWER") (class "Default")
      (node (ref "C1") (pin "2") (pinfunction "2_2") (pintype "passive"))
      (node (ref "C4") (pin "1") (pinfunction "1_1") (pintype "passive"))
      (node (ref "CP1") (pin "2") (pinfunction "New_2") (pintype "passive"))
      (node (ref "U2") (pin "3") (pinfunction "IN_3") (pintype "power_in"))
      (node (ref "U7") (pin "1") (pinfunction "Vcc_1") (pintype "passive"))
    )
    (net (code "69") (name "V_USB") (class "Default")
      (node (ref "C12") (pin "2") (pinfunction "2_2") (pintype "passive"))
      (node (ref "J1") (pin "1") (pinfunction "5V_1") (pintype "power_in"))
      (node (ref "P2") (pin "3") (pinfunction "3_3") (pintype "passive"))
    )
    (net (code "70") (name "unconnected-(CP1-PowerOld-Pad3)") (class "Default")
      (node (ref "CP1") (pin "3") (pinfunction "PowerOld_3") (pintype "passive+no_connect"))
    )
    (net (code "71") (name "unconnected-(J1-ID-Pad4)") (class "Default")
      (node (ref "J1") (pin "4") (pinfunction "ID_4") (pintype "passive"))
    )
    (net (code "72") (name "unconnected-(P5-Pad3)") (class "Default")
      (node (ref "P5") (pin "3") (pinfunction "3_3") (pintype "passive"))
    )
    (net (code "73") (name "unconnected-(P5-Pad4)") (class "Default")
      (node (ref "P5") (pin "4") (pinfunction "4_4") (pintype "passive"))
    )
    (net (code "74") (name "unconnected-(U5-AIO0-Pad9)") (class "Default")
      (node (ref "U5") (pin "9") (pinfunction "AIO0_9") (pintype "passive+no_connect"))
    )
    (net (code "75") (name "unconnected-(U5-AIO1-Pad10)") (class "Default")
      (node (ref "U5") (pin "10") (pinfunction "AIO1_10") (pintype "passive+no_connect"))
    )
    (net (code "76") (name "unconnected-(U5-CLK-Pad19)") (class "Default")
      (node (ref "U5") (pin "19") (pinfunction "CLK_19") (pintype "passive+no_connect"))
    )
    (net (code "77") (name "unconnected-(U5-CSB-Pad16)") (class "Default")
      (node (ref "U5") (pin "16") (pinfunction "CSB_16") (pintype "passive+no_connect"))
    )
    (net (code "78") (name "unconnected-(U5-CTS-Pad3)") (class "Default")
      (node (ref "U5") (pin "3") (pinfunction "CTS_3") (pintype "passive+no_connect"))
    )
    (net (code "79") (name "unconnected-(U5-MISO-Pad18)") (class "Default")
      (node (ref "U5") (pin "18") (pinfunction "MISO_18") (pintype "passive+no_connect"))
    )
    (net (code "80") (name "unconnected-(U5-MOSI-Pad17)") (class "Default")
      (node (ref "U5") (pin "17") (pinfunction "MOSI_17") (pintype "passive+no_connect"))
    )
    (net (code "81") (name "unconnected-(U5-NC-Pad14)") (class "Default")
      (node (ref "U5") (pin "14") (pinfunction "NC_14") (pintype "passive+no_connect"))
    )
    (net (code "82") (name "unconnected-(U5-PCM_CLK-Pad5)") (class "Default")
      (node (ref "U5") (pin "5") (pinfunction "PCM_CLK_5") (pintype "passive+no_connect"))
    )
    (net (code "83") (name "unconnected-(U5-PCM_IN-Pad7)") (class "Default")
      (node (ref "U5") (pin "7") (pinfunction "PCM_IN_7") (pintype "passive+no_connect"))
    )
    (net (code "84") (name "unconnected-(U5-PCM_OUT-Pad6)") (class "Default")
      (node (ref "U5") (pin "6") (pinfunction "PCM_OUT_6") (pintype "passive+no_connect"))
    )
    (net (code "85") (name "unconnected-(U5-PCM_SYNC-Pad8)") (class "Default")
      (node (ref "U5") (pin "8") (pinfunction "PCM_SYNC_8") (pintype "passive+no_connect"))
    )
    (net (code "86") (name "unconnected-(U5-PIO0-Pad23)") (class "Default")
      (node (ref "U5") (pin "23") (pinfunction "PIO0_23") (pintype "passive+no_connect"))
    )
    (net (code "87") (name "unconnected-(U5-PIO1-Pad24)") (class "Default")
      (node (ref "U5") (pin "24") (pinfunction "PIO1_24") (pintype "passive+no_connect"))
    )
    (net (code "88") (name "unconnected-(U5-PIO2-Pad25)") (class "Default")
      (node (ref "U5") (pin "25") (pinfunction "PIO2_25") (pintype "passive+no_connect"))
    )
    (net (code "89") (name "unconnected-(U5-PIO3-Pad26)") (class "Default")
      (node (ref "U5") (pin "26") (pinfunction "PIO3_26") (pintype "passive+no_connect"))
    )
    (net (code "90") (name "unconnected-(U5-PIO4-Pad27)") (class "Default")
      (node (ref "U5") (pin "27") (pinfunction "PIO4_27") (pintype "passive+no_connect"))
    )
    (net (code "91") (name "unconnected-(U5-PIO5-Pad28)") (class "Default")
      (node (ref "U5") (pin "28") (pinfunction "PIO5_28") (pintype "passive+no_connect"))
    )
    (net (code "92") (name "unconnected-(U5-PIO6-Pad29)") (class "Default")
      (node (ref "U5") (pin "29") (pinfunction "PIO6_29") (pintype "passive+no_connect"))
    )
    (net (code "93") (name "unconnected-(U5-PIO7-Pad30)") (class "Default")
      (node (ref "U5") (pin "30") (pinfunction "PIO7_30") (pintype "passive+no_connect"))
    )
    (net (code "94") (name "unconnected-(U5-PIO10-Pad33)") (class "Default")
      (node (ref "U5") (pin "33") (pinfunction "PIO10_33") (pintype "passive+no_connect"))
    )
    (net (code "95") (name "unconnected-(U5-RESET-Pad11)") (class "Default")
      (node (ref "U5") (pin "11") (pinfunction "RESET_11") (pintype "passive"))
    )
    (net (code "96") (name "unconnected-(U5-RTS-Pad4)") (class "Default")
      (node (ref "U5") (pin "4") (pinfunction "RTS_4") (pintype "passive+no_connect"))
    )
    (net (code "97") (name "unconnected-(U5-USB_DM-Pad15)") (class "Default")
      (node (ref "U5") (pin "15") (pinfunction "USB_DM_15") (pintype "passive+no_connect"))
    )
    (net (code "98") (name "unconnected-(U5-USB_DP-Pad20)") (class "Default")
      (node (ref "U5") (pin "20") (pinfunction "USB_DP_20") (pintype "passive+no_connect"))
    )
    (net (code "99") (name "unconnected-(U6-PD0{slash}SYNC{slash}OC0A-Pad20)") (class "Default")
      (node (ref "U6") (pin "20") (pinfunction "PD0/SYNC/OC0A_20") (pintype "bidirectional+no_connect"))
    )
  )
)
